# MAIN.net
KiCad netlist of a schematic drawn in Altium Designer
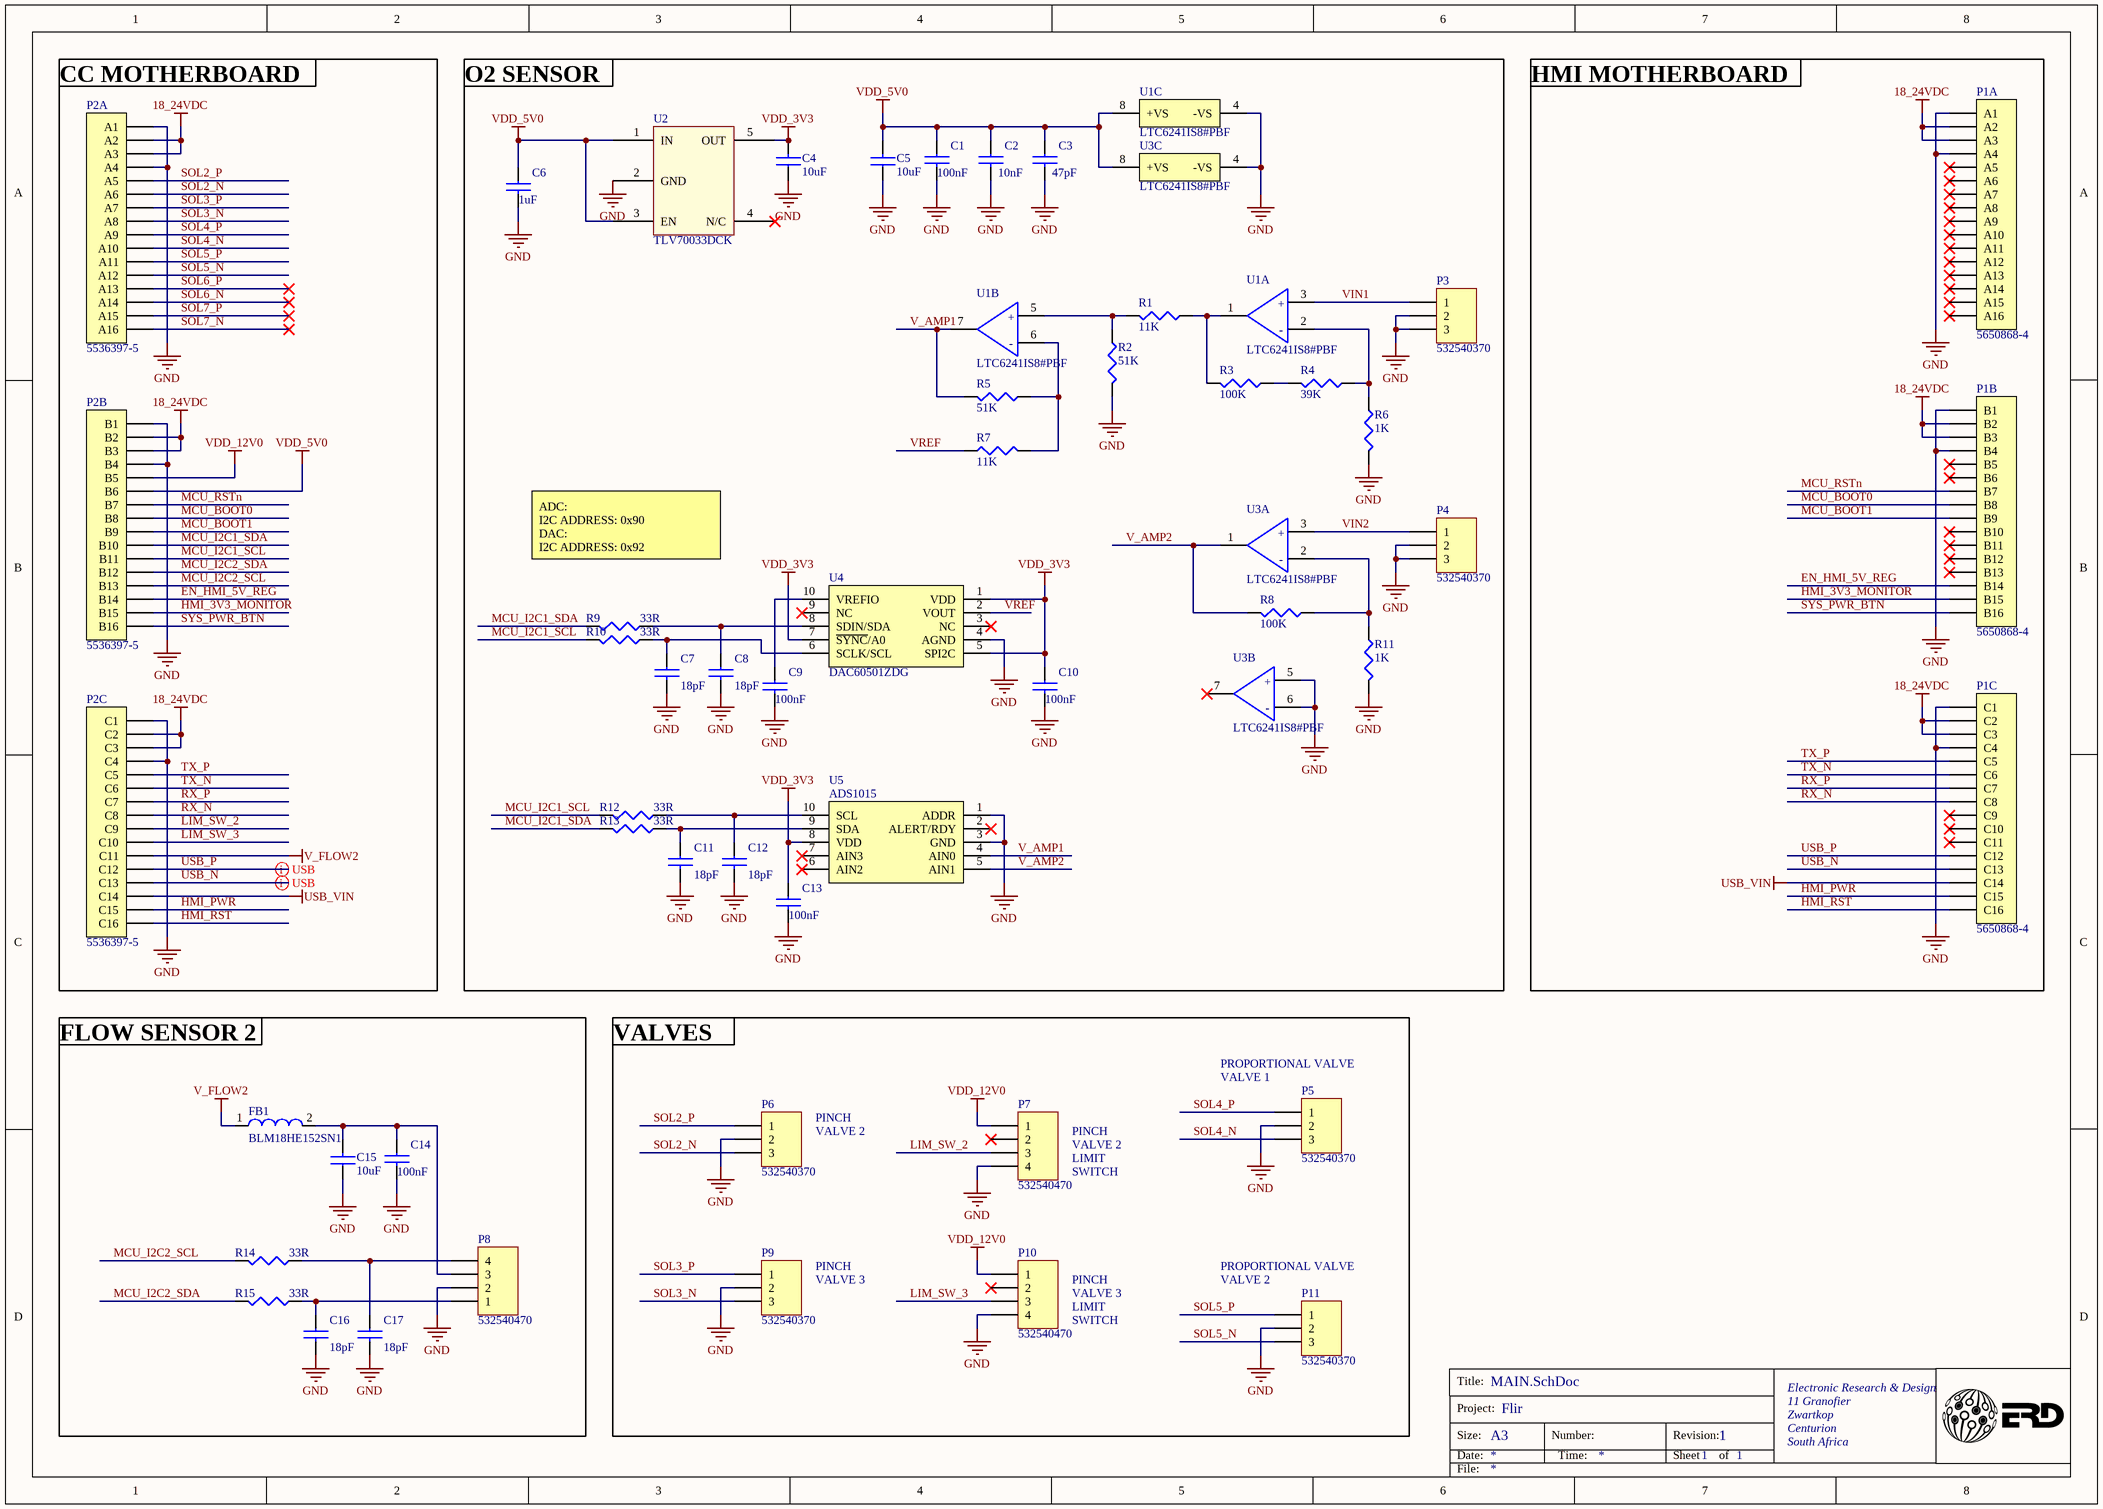
[diagram p0: MAIN.SchDoc]

(export (version "E")
  (design (tool "Eeschema 10.0.6"))
  (components
    (comp (ref "C1")
      (value "100nF")
      (footprint "CC0402")
      (description "CAP CER 0.1UF 50V 10% X7R 0402")
      (fields (field (name "MANUFACTURER") "Murata") (field (name "PART NUMBER") "GCM155R71H104KE02D"))
      (libsource (lib "ERD TiAm") (part "CAP CER 0.1UF 10V 10% X5R 0402"))
    )
    (comp (ref "C2")
      (value "10nF")
      (footprint "CC0402")
      (description "CAP CER 10NF 50V 10% X7R 0402")
      (fields (field (name "MANUFACTURER") "Murata") (field (name "PART NUMBER") "GRM155R71H103KA88J"))
      (libsource (lib "ERD TiAm") (part "CAP CER 0.1UF 10V 10% X5R 0402"))
    )
    (comp (ref "C3")
      (value "47pF")
      (footprint "CC0402")
      (description "CAP CER 47PF 50V 5% C0G/NP0 0402")
      (fields (field (name "MANUFACTURER") "Murata") (field (name "PART NUMBER") "GCM1555C1H470JA16D"))
      (libsource (lib "ERD TiAm") (part "CAP CER 0.1UF 10V 10% X5R 0402"))
    )
    (comp (ref "C4")
      (value "10uF")
      (footprint "CC0603")
      (description "CAP CER 10UF 25V 20% X5R 0603")
      (fields (field (name "MANUFACTURER") "Murata") (field (name "PARTNUMBER") "GRM188R61E106MA73D"))
      (libsource (lib "ERD TiAm") (part "CAP CER 0.1UF 10V 10% X5R 0402"))
    )
    (comp (ref "C5")
      (value "10uF")
      (footprint "CC0603")
      (description "CAP CER 10UF 25V 20% X5R 0603")
      (fields (field (name "MANUFACTURER") "Murata") (field (name "PARTNUMBER") "GRM188R61E106MA73D"))
      (libsource (lib "ERD TiAm") (part "CAP CER 0.1UF 10V 10% X5R 0402"))
    )
    (comp (ref "C6")
      (value "1uF")
      (footprint "CC0402")
      (description "CAP CER 1UF 10V 20% X5R 0402")
      (fields (field (name "MANUFACTURER") "Murata") (field (name "PART NUMBER") "GRM153R61A105ME95D"))
      (libsource (lib "ERD TiAm") (part "CAP CER 0.1UF 10V 10% X5R 0402"))
    )
    (comp (ref "C7")
      (value "18pF")
      (footprint "CC0402")
      (description "CAP CER 18pF 50V 5% C0G 0402")
      (fields (field (name "MANUFACTURER") "AVX") (field (name "PARTNUMBER") "GJM1555C1H180FB01D"))
      (libsource (lib "ERD TiAm") (part "CAP CER 2.2UF 6.3V 10% X5R 0402"))
    )
    (comp (ref "C8")
      (value "18pF")
      (footprint "CC0402")
      (description "CAP CER 18pF 50V 5% C0G 0402")
      (fields (field (name "MANUFACTURER") "AVX") (field (name "PARTNUMBER") "GJM1555C1H180FB01D"))
      (libsource (lib "ERD TiAm") (part "CAP CER 2.2UF 6.3V 10% X5R 0402"))
    )
    (comp (ref "C9")
      (value "100nF")
      (footprint "CC0402")
      (description "CAP CER 0.1UF 50V 10% X7R 0402")
      (fields (field (name "MANUFACTURER") "Murata") (field (name "PART NUMBER") "GCM155R71H104KE02D"))
      (libsource (lib "ERD TiAm") (part "CAP CER 0.1UF 10V 10% X5R 0402"))
    )
    (comp (ref "C10")
      (value "100nF")
      (footprint "CC0402")
      (description "CAP CER 0.1UF 50V 10% X7R 0402")
      (fields (field (name "MANUFACTURER") "Murata") (field (name "PART NUMBER") "GCM155R71H104KE02D"))
      (libsource (lib "ERD TiAm") (part "CAP CER 0.1UF 10V 10% X5R 0402"))
    )
    (comp (ref "C11")
      (value "18pF")
      (footprint "CC0402")
      (description "CAP CER 18pF 50V 5% C0G 0402")
      (fields (field (name "MANUFACTURER") "AVX") (field (name "PARTNUMBER") "GJM1555C1H180FB01D"))
      (libsource (lib "ERD TiAm") (part "CAP CER 2.2UF 6.3V 10% X5R 0402"))
    )
    (comp (ref "C12")
      (value "18pF")
      (footprint "CC0402")
      (description "CAP CER 18pF 50V 5% C0G 0402")
      (fields (field (name "MANUFACTURER") "AVX") (field (name "PARTNUMBER") "GJM1555C1H180FB01D"))
      (libsource (lib "ERD TiAm") (part "CAP CER 2.2UF 6.3V 10% X5R 0402"))
    )
    (comp (ref "C13")
      (value "100nF")
      (footprint "CC0402")
      (description "CAP CER 0.1UF 50V 10% X7R 0402")
      (fields (field (name "MANUFACTURER") "Murata") (field (name "PART NUMBER") "GCM155R71H104KE02D"))
      (libsource (lib "ERD TiAm") (part "CAP CER 0.1UF 10V 10% X5R 0402"))
    )
    (comp (ref "C14")
      (value "100nF")
      (footprint "CC0402")
      (description "CAP CER 0.1UF 50V 10% X7R 0402")
      (fields (field (name "MANUFACTURER") "Murata") (field (name "PART NUMBER") "GCM155R71H104KE02D"))
      (libsource (lib "ERD TiAm") (part "CAP CER 0.1UF 10V 10% X5R 0402"))
    )
    (comp (ref "C15")
      (value "10uF")
      (footprint "CC0603")
      (description "CAP CER 10UF 25V 20% X5R 0603")
      (fields (field (name "MANUFACTURER") "Murata") (field (name "PARTNUMBER") "GRM188R61E106MA73D"))
      (libsource (lib "ERD TiAm") (part "CAP CER 0.1UF 10V 10% X5R 0402"))
    )
    (comp (ref "C16")
      (value "18pF")
      (footprint "CC0402")
      (description "CAP CER 18pF 50V 5% C0G 0402")
      (fields (field (name "MANUFACTURER") "AVX") (field (name "PARTNUMBER") "GJM1555C1H180FB01D"))
      (libsource (lib "ERD TiAm") (part "CAP CER 2.2UF 6.3V 10% X5R 0402"))
    )
    (comp (ref "C17")
      (value "18pF")
      (footprint "CC0402")
      (description "CAP CER 18pF 50V 5% C0G 0402")
      (fields (field (name "MANUFACTURER") "AVX") (field (name "PARTNUMBER") "GJM1555C1H180FB01D"))
      (libsource (lib "ERD TiAm") (part "CAP CER 2.2UF 6.3V 10% X5R 0402"))
    )
    (comp (ref "FB1")
      (value "BLM18HE152SN1")
      (footprint "LC0603")
      (description "FERRITE, 500mA, 500mOHM, 0603")
      (libsource (lib "BEAGLEBONEBLACK_REV A5B") (part "FER_180_200_0"))
    )
    (comp (ref "P1")
      (value "5650868-4")
      (footprint "5650868-4_F_RA")
      (description "DIN-41612, R/2, 48-circuit, 3x16, 2.54mm pitch, RA, TH")
      (fields (field (name "MANUFACTURER") "TE Connectivity"))
      (libsource (lib "ERD TiAm") (part "DIN_41612_3x16"))
    )
    (comp (ref "P2")
      (value "5536397-5")
      (description "DIN-41612, C/2, 48-circuit, 3x16, 2.54mm pitch, TH")
      (fields (field (name "MANUFACTURER") "TE CONNECTIVITY"))
      (libsource (lib "DIN_designator") (part "DIN_41612_3x16"))
    )
    (comp (ref "P3")
      (value "532540370")
      (footprint "HDR1X3")
      (description "Header, RA, 3-circuit, 2mm pitch, TH")
      (fields (field (name "MANUFACTURER") "Molex"))
      (libsource (lib "Miscellaneous Connectors") (part "Header 3"))
    )
    (comp (ref "P4")
      (value "532540370")
      (footprint "HDR1X3")
      (description "Header, RA, 3-circuit, 2mm pitch, TH")
      (fields (field (name "MANUFACTURER") "Molex"))
      (libsource (lib "Miscellaneous Connectors") (part "Header 3"))
    )
    (comp (ref "P5")
      (value "532540370")
      (footprint "HDR1X3")
      (description "Header, RA, 3-circuit, 2mm pitch, TH")
      (fields (field (name "MANUFACTURER") "Molex"))
      (libsource (lib "Miscellaneous Connectors") (part "Header 3"))
    )
    (comp (ref "P6")
      (value "532540370")
      (footprint "HDR1X3")
      (description "Header, RA, 3-circuit, 2mm pitch, TH")
      (fields (field (name "MANUFACTURER") "Molex"))
      (libsource (lib "Miscellaneous Connectors") (part "Header 3"))
    )
    (comp (ref "P7")
      (value "532540470")
      (footprint "HDR1X4")
      (description "Header, RA, 4-circuit, 2mm pitch, TH")
      (fields (field (name "MANUFACTURER") "Molex"))
      (libsource (lib "Miscellaneous Connectors") (part "Header 4"))
    )
    (comp (ref "P8")
      (value "532540470")
      (footprint "HDR1X4")
      (description "Header, RA, 4-circuit, 2mm pitch, TH")
      (fields (field (name "MANUFACTURER") "Molex"))
      (libsource (lib "") (part "Header 4_1"))
    )
    (comp (ref "P9")
      (value "532540370")
      (footprint "HDR1X3")
      (description "Header, RA, 3-circuit, 2mm pitch, TH")
      (fields (field (name "MANUFACTURER") "Molex"))
      (libsource (lib "Miscellaneous Connectors") (part "Header 3"))
    )
    (comp (ref "P10")
      (value "532540470")
      (footprint "HDR1X4")
      (description "Header, RA, 4-circuit, 2mm pitch, TH")
      (fields (field (name "MANUFACTURER") "Molex"))
      (libsource (lib "Miscellaneous Connectors") (part "Header 4"))
    )
    (comp (ref "P11")
      (value "532540370")
      (footprint "HDR1X3")
      (description "Header, RA, 3-circuit, 2mm pitch, TH")
      (fields (field (name "MANUFACTURER") "Molex"))
      (libsource (lib "Miscellaneous Connectors") (part "Header 3"))
    )
    (comp (ref "R1")
      (value "11K")
      (footprint "RC0402")
      (description "RES, 11K OHM, 1/16W, 1%, 0402")
      (fields (field (name "MANUFACTURER") "Yageo") (field (name "PARTNUMBER") "RC0402FR-0711KL"))
      (libsource (lib "ERD TiAm") (part "RES_10K_1/16W_1%_0402"))
    )
    (comp (ref "R2")
      (value "51K")
      (footprint "RC0402")
      (description "RES, 51K OHM, 1/16W, 1%, 0402")
      (fields (field (name "MANUFACTURER") "Yageo") (field (name "PARTNUMBER") "RC0402FR-0751KL"))
      (libsource (lib "ERD TiAm") (part "RES_10K_1/16W_1%_0402"))
    )
    (comp (ref "R3")
      (value "100K")
      (footprint "RC0402")
      (description "RES, 100K OHM, 1/16W, 1%, 0402")
      (fields (field (name "MANUFACTURER") "Yageo") (field (name "PARTNUMBER") "RC0402FR-07100KL"))
      (libsource (lib "ERD TiAm") (part "RES_10K_1/16W_1%_0402"))
    )
    (comp (ref "R4")
      (value "39K")
      (footprint "RC0402")
      (description "RES, 39K OHM, 1/16W, 1%, 0402")
      (fields (field (name "MANUFACTURER") "Yageo") (field (name "PARTNUMBER") "RC0402FR-0739KL"))
      (libsource (lib "ERD TiAm") (part "RES_10K_1/16W_1%_0402"))
    )
    (comp (ref "R5")
      (value "51K")
      (footprint "RC0402")
      (description "RES, 51K OHM, 1/16W, 1%, 0402")
      (fields (field (name "MANUFACTURER") "Yageo") (field (name "PARTNUMBER") "RC0402FR-0751KL"))
      (libsource (lib "ERD TiAm") (part "RES_10K_1/16W_1%_0402"))
    )
    (comp (ref "R6")
      (value "1K")
      (footprint "RC0402")
      (description "RES, 1K OHM, 1/16W, 1%, 0402")
      (fields (field (name "MANUFACTURER") "Yageo") (field (name "PARTNUMBER") "RC0402FR-071KL"))
      (libsource (lib "ERD TiAm") (part "RES_10K_1/16W_1%_0402"))
    )
    (comp (ref "R7")
      (value "11K")
      (footprint "RC0402")
      (description "RES, 11K OHM, 1/16W, 1%, 0402")
      (fields (field (name "MANUFACTURER") "Yageo") (field (name "PARTNUMBER") "RC0402FR-0711KL"))
      (libsource (lib "ERD TiAm") (part "RES_10K_1/16W_1%_0402"))
    )
    (comp (ref "R8")
      (value "100K")
      (footprint "RC0402")
      (description "RES, 100K OHM, 1/16W, 1%, 0402")
      (fields (field (name "MANUFACTURER") "Yageo") (field (name "PARTNUMBER") "RC0402FR-07100KL"))
      (libsource (lib "ERD TiAm") (part "RES_10K_1/16W_1%_0402"))
    )
    (comp (ref "R9")
      (value "33R")
      (footprint "RC0402")
      (description "RES, 33 OHM, 1/16W, 1%, 0402")
      (fields (field (name "MANUFACTURER") "Yageo") (field (name "PARTNUMBER") "RC0402FR-0733RL"))
      (libsource (lib "ERD TiAm") (part "RES_10K_1/16W_1%_0402"))
    )
    (comp (ref "R10")
      (value "33R")
      (footprint "RC0402")
      (description "RES, 33 OHM, 1/16W, 1%, 0402")
      (fields (field (name "MANUFACTURER") "Yageo") (field (name "PARTNUMBER") "RC0402FR-0733RL"))
      (libsource (lib "ERD TiAm") (part "RES_10K_1/16W_1%_0402"))
    )
    (comp (ref "R11")
      (value "1K")
      (footprint "RC0402")
      (description "RES, 1K OHM, 1/16W, 1%, 0402")
      (fields (field (name "MANUFACTURER") "Yageo") (field (name "PARTNUMBER") "RC0402FR-071KL"))
      (libsource (lib "ERD TiAm") (part "RES_10K_1/16W_1%_0402"))
    )
    (comp (ref "R12")
      (value "33R")
      (footprint "RC0402")
      (description "RES, 33 OHM, 1/16W, 1%, 0402")
      (fields (field (name "MANUFACTURER") "Yageo") (field (name "PARTNUMBER") "RC0402FR-0733RL"))
      (libsource (lib "ERD TiAm") (part "RES_10K_1/16W_1%_0402"))
    )
    (comp (ref "R13")
      (value "33R")
      (footprint "RC0402")
      (description "RES, 33 OHM, 1/16W, 1%, 0402")
      (fields (field (name "MANUFACTURER") "Yageo") (field (name "PARTNUMBER") "RC0402FR-0733RL"))
      (libsource (lib "ERD TiAm") (part "RES_10K_1/16W_1%_0402"))
    )
    (comp (ref "R14")
      (value "33R")
      (footprint "RC0402")
      (description "RES, 33 OHM, 1/16W, 1%, 0402")
      (fields (field (name "MANUFACTURER") "Yageo") (field (name "PARTNUMBER") "RC0402FR-0733RL"))
      (libsource (lib "ERD TiAm") (part "RES_10K_1/16W_1%_0402"))
    )
    (comp (ref "R15")
      (value "33R")
      (footprint "RC0402")
      (description "RES, 33 OHM, 1/16W, 1%, 0402")
      (fields (field (name "MANUFACTURER") "Yageo") (field (name "PARTNUMBER") "RC0402FR-0733RL"))
      (libsource (lib "ERD TiAm") (part "RES_10K_1/16W_1%_0402"))
    )
    (comp (ref "U1")
      (value "LTC6241IS8#PBF")
      (footprint "SOIC-8")
      (description "Op-AMP, Dual, 18MHz, SOIC-8")
      (libsource (lib "") (part "AD823A_1"))
    )
    (comp (ref "U2")
      (value "TLV70033DCK")
      (footprint "SC-70-5")
      (description "LDO, 3.3V, 200mA, SC70-5")
      (libsource (lib "CameraModule") (part "TLV700"))
    )
    (comp (ref "U3")
      (value "LTC6241IS8#PBF")
      (footprint "SOIC-8")
      (description "Op-AMP, Dual, 18MHz, SOIC-8")
      (libsource (lib "") (part "AD823A_1"))
    )
    (comp (ref "U4")
      (value "DAC60501ZDG")
      (footprint "VSSOP-10")
      (description "DAC, 12-bit, I2C, VSSOP-10")
      (libsource (lib "ERD TiAm") (part "DAC60501"))
    )
    (comp (ref "U5")
      (value "ADS1015")
      (footprint "VSSOP-10")
      (description "ADC, 12-bit, I2C, 4-channel, VSSOP-10")
      (libsource (lib "ERD TiAm") (part "ADS1015"))
    )
  )
  (nets
    (net (code "1") (name "/EN_HMI_5V_REG") (class "Default")
      (node (ref "P1") (pin "30") (pinfunction "B14_30") (pintype "passive"))
      (node (ref "P2") (pin "30") (pinfunction "B14_30") (pintype "passive"))
    )
    (net (code "2") (name "/HMI_3V3_MONITOR") (class "Default")
      (node (ref "P1") (pin "31") (pinfunction "B15_31") (pintype "passive"))
      (node (ref "P2") (pin "31") (pinfunction "B15_31") (pintype "passive"))
    )
    (net (code "3") (name "/HMI_PWR") (class "Default")
      (node (ref "P1") (pin "47") (pinfunction "C15_47") (pintype "passive"))
      (node (ref "P2") (pin "47") (pinfunction "C15_47") (pintype "passive"))
    )
    (net (code "4") (name "/HMI_RST") (class "Default")
      (node (ref "P1") (pin "48") (pinfunction "C16_48") (pintype "passive"))
      (node (ref "P2") (pin "48") (pinfunction "C16_48") (pintype "passive"))
    )
    (net (code "5") (name "/LIM_SW_2") (class "Default")
      (node (ref "P2") (pin "41") (pinfunction "C9_41") (pintype "passive"))
      (node (ref "P7") (pin "3") (pinfunction "3_3") (pintype "passive"))
    )
    (net (code "6") (name "/LIM_SW_3") (class "Default")
      (node (ref "P10") (pin "3") (pinfunction "3_3") (pintype "passive"))
      (node (ref "P2") (pin "42") (pinfunction "C10_42") (pintype "passive"))
    )
    (net (code "7") (name "/MCU_BOOT0") (class "Default")
      (node (ref "P1") (pin "24") (pinfunction "B8_24") (pintype "passive"))
      (node (ref "P2") (pin "24") (pinfunction "B8_24") (pintype "passive"))
    )
    (net (code "8") (name "/MCU_BOOT1") (class "Default")
      (node (ref "P1") (pin "25") (pinfunction "B9_25") (pintype "passive"))
      (node (ref "P2") (pin "25") (pinfunction "B9_25") (pintype "passive"))
    )
    (net (code "9") (name "/MCU_I2C1_SCL") (class "Default")
      (node (ref "P2") (pin "27") (pinfunction "B11_27") (pintype "passive"))
      (node (ref "R10") (pin "2") (pinfunction "2_2") (pintype "passive"))
      (node (ref "R12") (pin "2") (pinfunction "2_2") (pintype "passive"))
    )
    (net (code "10") (name "/MCU_I2C1_SDA") (class "Default")
      (node (ref "P2") (pin "26") (pinfunction "B10_26") (pintype "passive"))
      (node (ref "R13") (pin "2") (pinfunction "2_2") (pintype "passive"))
      (node (ref "R9") (pin "2") (pinfunction "2_2") (pintype "passive"))
    )
    (net (code "11") (name "/MCU_I2C2_SCL") (class "Default")
      (node (ref "P2") (pin "29") (pinfunction "B13_29") (pintype "passive"))
      (node (ref "R14") (pin "2") (pinfunction "2_2") (pintype "passive"))
    )
    (net (code "12") (name "/MCU_I2C2_SDA") (class "Default")
      (node (ref "P2") (pin "28") (pinfunction "B12_28") (pintype "passive"))
      (node (ref "R15") (pin "2") (pinfunction "2_2") (pintype "passive"))
    )
    (net (code "13") (name "/MCU_RSTn") (class "Default")
      (node (ref "P1") (pin "23") (pinfunction "B7_23") (pintype "passive"))
      (node (ref "P2") (pin "23") (pinfunction "B7_23") (pintype "passive"))
    )
    (net (code "14") (name "/RX_N") (class "Default")
      (node (ref "P1") (pin "40") (pinfunction "C8_40") (pintype "passive"))
      (node (ref "P2") (pin "40") (pinfunction "C8_40") (pintype "passive"))
    )
    (net (code "15") (name "/RX_P") (class "Default")
      (node (ref "P1") (pin "39") (pinfunction "C7_39") (pintype "passive"))
      (node (ref "P2") (pin "39") (pinfunction "C7_39") (pintype "passive"))
    )
    (net (code "16") (name "/SOL2_N") (class "Default")
      (node (ref "P2") (pin "6") (pinfunction "A6_6") (pintype "passive"))
      (node (ref "P6") (pin "3") (pinfunction "3_3") (pintype "passive"))
    )
    (net (code "17") (name "/SOL2_P") (class "Default")
      (node (ref "P2") (pin "5") (pinfunction "A5_5") (pintype "passive"))
      (node (ref "P6") (pin "1") (pinfunction "1_1") (pintype "passive"))
    )
    (net (code "18") (name "/SOL3_N") (class "Default")
      (node (ref "P2") (pin "8") (pinfunction "A8_8") (pintype "passive"))
      (node (ref "P9") (pin "3") (pinfunction "3_3") (pintype "passive"))
    )
    (net (code "19") (name "/SOL3_P") (class "Default")
      (node (ref "P2") (pin "7") (pinfunction "A7_7") (pintype "passive"))
      (node (ref "P9") (pin "1") (pinfunction "1_1") (pintype "passive"))
    )
    (net (code "20") (name "/SOL4_N") (class "Default")
      (node (ref "P2") (pin "10") (pinfunction "A10_10") (pintype "passive"))
      (node (ref "P5") (pin "3") (pinfunction "3_3") (pintype "passive"))
    )
    (net (code "21") (name "/SOL4_P") (class "Default")
      (node (ref "P2") (pin "9") (pinfunction "A9_9") (pintype "passive"))
      (node (ref "P5") (pin "1") (pinfunction "1_1") (pintype "passive"))
    )
    (net (code "22") (name "/SOL5_N") (class "Default")
      (node (ref "P11") (pin "3") (pinfunction "3_3") (pintype "passive"))
      (node (ref "P2") (pin "12") (pinfunction "A12_12") (pintype "passive"))
    )
    (net (code "23") (name "/SOL5_P") (class "Default")
      (node (ref "P11") (pin "1") (pinfunction "1_1") (pintype "passive"))
      (node (ref "P2") (pin "11") (pinfunction "A11_11") (pintype "passive"))
    )
    (net (code "24") (name "/SOL6_N") (class "Default")
      (node (ref "P2") (pin "14") (pinfunction "A14_14") (pintype "passive+no_connect"))
    )
    (net (code "25") (name "/SOL6_P") (class "Default")
      (node (ref "P2") (pin "13") (pinfunction "A13_13") (pintype "passive+no_connect"))
    )
    (net (code "26") (name "/SOL7_N") (class "Default")
      (node (ref "P2") (pin "16") (pinfunction "A16_16") (pintype "passive+no_connect"))
    )
    (net (code "27") (name "/SOL7_P") (class "Default")
      (node (ref "P2") (pin "15") (pinfunction "A15_15") (pintype "passive+no_connect"))
    )
    (net (code "28") (name "/SYS_PWR_BTN") (class "Default")
      (node (ref "P1") (pin "32") (pinfunction "B16_32") (pintype "passive"))
      (node (ref "P2") (pin "32") (pinfunction "B16_32") (pintype "passive"))
    )
    (net (code "29") (name "/TX_N") (class "Default")
      (node (ref "P1") (pin "38") (pinfunction "C6_38") (pintype "passive"))
      (node (ref "P2") (pin "38") (pinfunction "C6_38") (pintype "passive"))
    )
    (net (code "30") (name "/TX_P") (class "Default")
      (node (ref "P1") (pin "37") (pinfunction "C5_37") (pintype "passive"))
      (node (ref "P2") (pin "37") (pinfunction "C5_37") (pintype "passive"))
    )
    (net (code "31") (name "/USB_N") (class "Default")
      (node (ref "P1") (pin "45") (pinfunction "C13_45") (pintype "passive"))
      (node (ref "P2") (pin "45") (pinfunction "C13_45") (pintype "passive"))
    )
    (net (code "32") (name "/USB_P") (class "Default")
      (node (ref "P1") (pin "44") (pinfunction "C12_44") (pintype "passive"))
      (node (ref "P2") (pin "44") (pinfunction "C12_44") (pintype "passive"))
    )
    (net (code "33") (name "/VIN1") (class "Default")
      (node (ref "P3") (pin "1") (pinfunction "1_1") (pintype "passive"))
      (node (ref "U1") (pin "3") (pinfunction "+IN1_3") (pintype "passive"))
    )
    (net (code "34") (name "/VIN2") (class "Default")
      (node (ref "P4") (pin "1") (pinfunction "1_1") (pintype "passive"))
      (node (ref "U3") (pin "3") (pinfunction "+IN1_3") (pintype "passive"))
    )
    (net (code "35") (name "/VREF") (class "Default")
      (node (ref "R7") (pin "1") (pinfunction "1_1") (pintype "passive"))
      (node (ref "U4") (pin "2") (pinfunction "VOUT_2") (pintype "passive"))
    )
    (net (code "36") (name "/V_AMP1") (class "Default")
      (node (ref "R5") (pin "2") (pinfunction "2_2") (pintype "passive"))
      (node (ref "U1") (pin "7") (pinfunction "OUT2_7") (pintype "passive"))
      (node (ref "U5") (pin "4") (pinfunction "AIN0_4") (pintype "passive"))
    )
    (net (code "37") (name "/V_AMP2") (class "Default")
      (node (ref "R8") (pin "2") (pinfunction "2_2") (pintype "passive"))
      (node (ref "U3") (pin "1") (pinfunction "OUT1_1") (pintype "passive"))
      (node (ref "U5") (pin "5") (pinfunction "AIN1_5") (pintype "passive"))
    )
    (net (code "38") (name "18_24VDC") (class "Default")
      (node (ref "P1") (pin "18") (pinfunction "B2_18") (pintype "passive"))
      (node (ref "P1") (pin "19") (pinfunction "B3_19") (pintype "passive"))
      (node (ref "P1") (pin "2") (pinfunction "A2_2") (pintype "passive"))
      (node (ref "P1") (pin "3") (pinfunction "A3_3") (pintype "passive"))
      (node (ref "P1") (pin "34") (pinfunction "C2_34") (pintype "passive"))
      (node (ref "P1") (pin "35") (pinfunction "C3_35") (pintype "passive"))
      (node (ref "P2") (pin "18") (pinfunction "B2_18") (pintype "passive"))
      (node (ref "P2") (pin "19") (pinfunction "B3_19") (pintype "passive"))
      (node (ref "P2") (pin "2") (pinfunction "A2_2") (pintype "passive"))
      (node (ref "P2") (pin "3") (pinfunction "A3_3") (pintype "passive"))
      (node (ref "P2") (pin "34") (pinfunction "C2_34") (pintype "passive"))
      (node (ref "P2") (pin "35") (pinfunction "C3_35") (pintype "passive"))
    )
    (net (code "39") (name "GND") (class "Default")
      (node (ref "C1") (pin "2") (pinfunction "2_2") (pintype "passive"))
      (node (ref "C10") (pin "2") (pinfunction "2_2") (pintype "passive"))
      (node (ref "C11") (pin "2") (pinfunction "2_2") (pintype "passive"))
      (node (ref "C12") (pin "2") (pinfunction "2_2") (pintype "passive"))
      (node (ref "C13") (pin "2") (pinfunction "2_2") (pintype "passive"))
      (node (ref "C14") (pin "2") (pinfunction "2_2") (pintype "passive"))
      (node (ref "C15") (pin "1") (pinfunction "1_1") (pintype "passive"))
      (node (ref "C16") (pin "2") (pinfunction "2_2") (pintype "passive"))
      (node (ref "C17") (pin "2") (pinfunction "2_2") (pintype "passive"))
      (node (ref "C2") (pin "2") (pinfunction "2_2") (pintype "passive"))
      (node (ref "C3") (pin "2") (pinfunction "2_2") (pintype "passive"))
      (node (ref "C4") (pin "1") (pinfunction "1_1") (pintype "passive"))
      (node (ref "C5") (pin "1") (pinfunction "1_1") (pintype "passive"))
      (node (ref "C6") (pin "2") (pinfunction "2_2") (pintype "passive"))
      (node (ref "C7") (pin "2") (pinfunction "2_2") (pintype "passive"))
      (node (ref "C8") (pin "2") (pinfunction "2_2") (pintype "passive"))
      (node (ref "C9") (pin "2") (pinfunction "2_2") (pintype "passive"))
      (node (ref "P1") (pin "1") (pinfunction "A1_1") (pintype "passive"))
      (node (ref "P1") (pin "17") (pinfunction "B1_17") (pintype "passive"))
      (node (ref "P1") (pin "20") (pinfunction "B4_20") (pintype "passive"))
      (node (ref "P1") (pin "33") (pinfunction "C1_33") (pintype "passive"))
      (node (ref "P1") (pin "36") (pinfunction "C4_36") (pintype "passive"))
      (node (ref "P1") (pin "4") (pinfunction "A4_4") (pintype "passive"))
      (node (ref "P10") (pin "4") (pinfunction "4_4") (pintype "passive"))
      (node (ref "P11") (pin "2") (pinfunction "2_2") (pintype "passive"))
      (node (ref "P2") (pin "1") (pinfunction "A1_1") (pintype "passive"))
      (node (ref "P2") (pin "17") (pinfunction "B1_17") (pintype "passive"))
      (node (ref "P2") (pin "20") (pinfunction "B4_20") (pintype "passive"))
      (node (ref "P2") (pin "33") (pinfunction "C1_33") (pintype "passive"))
      (node (ref "P2") (pin "36") (pinfunction "C4_36") (pintype "passive"))
      (node (ref "P2") (pin "4") (pinfunction "A4_4") (pintype "passive"))
      (node (ref "P3") (pin "2") (pinfunction "2_2") (pintype "passive"))
      (node (ref "P3") (pin "3") (pinfunction "3_3") (pintype "passive"))
      (node (ref "P4") (pin "2") (pinfunction "2_2") (pintype "passive"))
      (node (ref "P4") (pin "3") (pinfunction "3_3") (pintype "passive"))
      (node (ref "P5") (pin "2") (pinfunction "2_2") (pintype "passive"))
      (node (ref "P6") (pin "2") (pinfunction "2_2") (pintype "passive"))
      (node (ref "P7") (pin "4") (pinfunction "4_4") (pintype "passive"))
      (node (ref "P8") (pin "2") (pinfunction "2_2") (pintype "passive"))
      (node (ref "P9") (pin "2") (pinfunction "2_2") (pintype "passive"))
      (node (ref "R11") (pin "2") (pinfunction "2_2") (pintype "passive"))
      (node (ref "R2") (pin "2") (pinfunction "2_2") (pintype "passive"))
      (node (ref "R6") (pin "2") (pinfunction "2_2") (pintype "passive"))
      (node (ref "U1") (pin "4") (pinfunction "-VS_4") (pintype "passive"))
      (node (ref "U2") (pin "2") (pinfunction "GND_2") (pintype "passive"))
      (node (ref "U3") (pin "4") (pinfunction "-VS_4") (pintype "passive"))
      (node (ref "U3") (pin "5") (pinfunction "+IN2_5") (pintype "passive"))
      (node (ref "U3") (pin "6") (pinfunction "-IN2_6") (pintype "passive"))
      (node (ref "U4") (pin "4") (pinfunction "AGND_4") (pintype "passive"))
      (node (ref "U5") (pin "1") (pinfunction "ADDR_1") (pintype "passive"))
      (node (ref "U5") (pin "3") (pinfunction "GND_3") (pintype "passive"))
    )
    (net (code "40") (name "Net-(C14-Pad1)") (class "Default")
      (node (ref "C14") (pin "1") (pinfunction "1_1") (pintype "passive"))
      (node (ref "C15") (pin "2") (pinfunction "2_2") (pintype "passive"))
      (node (ref "FB1") (pin "2") (pinfunction "2_2") (pintype "passive"))
      (node (ref "P8") (pin "3") (pinfunction "3_3") (pintype "passive"))
    )
    (net (code "41") (name "Net-(C16-Pad1)") (class "Default")
      (node (ref "C16") (pin "1") (pinfunction "1_1") (pintype "passive"))
      (node (ref "P8") (pin "1") (pinfunction "1_1") (pintype "passive"))
      (node (ref "R15") (pin "1") (pinfunction "1_1") (pintype "passive"))
    )
    (net (code "42") (name "Net-(C17-Pad1)") (class "Default")
      (node (ref "C17") (pin "1") (pinfunction "1_1") (pintype "passive"))
      (node (ref "P8") (pin "4") (pinfunction "4_4") (pintype "passive"))
      (node (ref "R14") (pin "1") (pinfunction "1_1") (pintype "passive"))
    )
    (net (code "43") (name "Net-(R3-Pad1)") (class "Default")
      (node (ref "R3") (pin "1") (pinfunction "1_1") (pintype "passive"))
      (node (ref "R4") (pin "2") (pinfunction "2_2") (pintype "passive"))
    )
    (net (code "44") (name "Net-(U1A--IN1)") (class "Default")
      (node (ref "R4") (pin "1") (pinfunction "1_1") (pintype "passive"))
      (node (ref "R6") (pin "1") (pinfunction "1_1") (pintype "passive"))
      (node (ref "U1") (pin "2") (pinfunction "-IN1_2") (pintype "passive"))
    )
    (net (code "45") (name "Net-(U1A-OUT1)") (class "Default")
      (node (ref "R1") (pin "1") (pinfunction "1_1") (pintype "passive"))
      (node (ref "R3") (pin "2") (pinfunction "2_2") (pintype "passive"))
      (node (ref "U1") (pin "1") (pinfunction "OUT1_1") (pintype "passive"))
    )
    (net (code "46") (name "Net-(U1B-+IN2)") (class "Default")
      (node (ref "R1") (pin "2") (pinfunction "2_2") (pintype "passive"))
      (node (ref "R2") (pin "1") (pinfunction "1_1") (pintype "passive"))
      (node (ref "U1") (pin "5") (pinfunction "+IN2_5") (pintype "passive"))
    )
    (net (code "47") (name "Net-(U1B--IN2)") (class "Default")
      (node (ref "R5") (pin "1") (pinfunction "1_1") (pintype "passive"))
      (node (ref "R7") (pin "2") (pinfunction "2_2") (pintype "passive"))
      (node (ref "U1") (pin "6") (pinfunction "-IN2_6") (pintype "passive"))
    )
    (net (code "48") (name "Net-(U3A--IN1)") (class "Default")
      (node (ref "R11") (pin "1") (pinfunction "1_1") (pintype "passive"))
      (node (ref "R8") (pin "1") (pinfunction "1_1") (pintype "passive"))
      (node (ref "U3") (pin "2") (pinfunction "-IN1_2") (pintype "passive"))
    )
    (net (code "49") (name "Net-(U4-SCLK{slash}SCL)") (class "Default")
      (node (ref "C7") (pin "1") (pinfunction "1_1") (pintype "passive"))
      (node (ref "R10") (pin "1") (pinfunction "1_1") (pintype "passive"))
      (node (ref "U4") (pin "6") (pinfunction "SCLK/SCL_6") (pintype "passive"))
    )
    (net (code "50") (name "Net-(U4-SDIN{slash}SDA)") (class "Default")
      (node (ref "C8") (pin "1") (pinfunction "1_1") (pintype "passive"))
      (node (ref "R9") (pin "1") (pinfunction "1_1") (pintype "passive"))
      (node (ref "U4") (pin "8") (pinfunction "SDIN/SDA_8") (pintype "passive"))
    )
    (net (code "51") (name "Net-(U4-VREFIO)") (class "Default")
      (node (ref "C9") (pin "1") (pinfunction "1_1") (pintype "passive"))
      (node (ref "U4") (pin "10") (pinfunction "VREFIO_10") (pintype "passive"))
    )
    (net (code "52") (name "Net-(U5-SCL)") (class "Default")
      (node (ref "C12") (pin "1") (pinfunction "1_1") (pintype "passive"))
      (node (ref "R12") (pin "1") (pinfunction "1_1") (pintype "passive"))
      (node (ref "U5") (pin "10") (pinfunction "SCL_10") (pintype "passive"))
    )
    (net (code "53") (name "Net-(U5-SDA)") (class "Default")
      (node (ref "C11") (pin "1") (pinfunction "1_1") (pintype "passive"))
      (node (ref "R13") (pin "1") (pinfunction "1_1") (pintype "passive"))
      (node (ref "U5") (pin "9") (pinfunction "SDA_9") (pintype "passive"))
    )
    (net (code "54") (name "USB_VIN") (class "Default")
      (node (ref "P1") (pin "46") (pinfunction "C14_46") (pintype "passive"))
      (node (ref "P2") (pin "46") (pinfunction "C14_46") (pintype "passive"))
    )
    (net (code "55") (name "VDD_3V3") (class "Default")
      (node (ref "C10") (pin "1") (pinfunction "1_1") (pintype "passive"))
      (node (ref "C13") (pin "1") (pinfunction "1_1") (pintype "passive"))
      (node (ref "C4") (pin "2") (pinfunction "2_2") (pintype "passive"))
      (node (ref "U2") (pin "5") (pinfunction "OUT_5") (pintype "passive"))
      (node (ref "U4") (pin "1") (pinfunction "VDD_1") (pintype "passive"))
      (node (ref "U4") (pin "5") (pinfunction "SPI2C_5") (pintype "passive"))
      (node (ref "U4") (pin "7") (pinfunction "~{SYNC}/A0_7") (pintype "passive"))
      (node (ref "U5") (pin "8") (pinfunction "VDD_8") (pintype "passive"))
    )
    (net (code "56") (name "VDD_5V0") (class "Default")
      (node (ref "C1") (pin "1") (pinfunction "1_1") (pintype "passive"))
      (node (ref "C2") (pin "1") (pinfunction "1_1") (pintype "passive"))
      (node (ref "C3") (pin "1") (pinfunction "1_1") (pintype "passive"))
      (node (ref "C5") (pin "2") (pinfunction "2_2") (pintype "passive"))
      (node (ref "C6") (pin "1") (pinfunction "1_1") (pintype "passive"))
      (node (ref "P2") (pin "22") (pinfunction "B6_22") (pintype "passive"))
      (node (ref "U1") (pin "8") (pinfunction "+VS_8") (pintype "passive"))
      (node (ref "U2") (pin "1") (pinfunction "IN_1") (pintype "passive"))
      (node (ref "U2") (pin "3") (pinfunction "EN_3") (pintype "passive"))
      (node (ref "U3") (pin "8") (pinfunction "+VS_8") (pintype "passive"))
    )
    (net (code "57") (name "VDD_12V0") (class "Default")
      (node (ref "P10") (pin "1") (pinfunction "1_1") (pintype "passive"))
      (node (ref "P2") (pin "21") (pinfunction "B5_21") (pintype "passive"))
      (node (ref "P7") (pin "1") (pinfunction "1_1") (pintype "passive"))
    )
    (net (code "58") (name "V_FLOW2") (class "Default")
      (node (ref "FB1") (pin "1") (pinfunction "1_1") (pintype "passive"))
      (node (ref "P2") (pin "43") (pinfunction "C11_43") (pintype "passive"))
    )
    (net (code "59") (name "unconnected-(P1A-A5-Pad5)") (class "Default")
      (node (ref "P1") (pin "5") (pinfunction "A5_5") (pintype "passive+no_connect"))
    )
    (net (code "60") (name "unconnected-(P1A-A6-Pad6)") (class "Default")
      (node (ref "P1") (pin "6") (pinfunction "A6_6") (pintype "passive+no_connect"))
    )
    (net (code "61") (name "unconnected-(P1A-A7-Pad7)") (class "Default")
      (node (ref "P1") (pin "7") (pinfunction "A7_7") (pintype "passive+no_connect"))
    )
    (net (code "62") (name "unconnected-(P1A-A8-Pad8)") (class "Default")
      (node (ref "P1") (pin "8") (pinfunction "A8_8") (pintype "passive+no_connect"))
    )
    (net (code "63") (name "unconnected-(P1A-A9-Pad9)") (class "Default")
      (node (ref "P1") (pin "9") (pinfunction "A9_9") (pintype "passive+no_connect"))
    )
    (net (code "64") (name "unconnected-(P1A-A10-Pad10)") (class "Default")
      (node (ref "P1") (pin "10") (pinfunction "A10_10") (pintype "passive+no_connect"))
    )
    (net (code "65") (name "unconnected-(P1A-A11-Pad11)") (class "Default")
      (node (ref "P1") (pin "11") (pinfunction "A11_11") (pintype "passive+no_connect"))
    )
    (net (code "66") (name "unconnected-(P1A-A12-Pad12)") (class "Default")
      (node (ref "P1") (pin "12") (pinfunction "A12_12") (pintype "passive+no_connect"))
    )
    (net (code "67") (name "unconnected-(P1A-A13-Pad13)") (class "Default")
      (node (ref "P1") (pin "13") (pinfunction "A13_13") (pintype "passive+no_connect"))
    )
    (net (code "68") (name "unconnected-(P1A-A14-Pad14)") (class "Default")
      (node (ref "P1") (pin "14") (pinfunction "A14_14") (pintype "passive+no_connect"))
    )
    (net (code "69") (name "unconnected-(P1A-A15-Pad15)") (class "Default")
      (node (ref "P1") (pin "15") (pinfunction "A15_15") (pintype "passive+no_connect"))
    )
    (net (code "70") (name "unconnected-(P1A-A16-Pad16)") (class "Default")
      (node (ref "P1") (pin "16") (pinfunction "A16_16") (pintype "passive+no_connect"))
    )
    (net (code "71") (name "unconnected-(P1B-B5-Pad21)") (class "Default")
      (node (ref "P1") (pin "21") (pinfunction "B5_21") (pintype "passive+no_connect"))
    )
    (net (code "72") (name "unconnected-(P1B-B6-Pad22)") (class "Default")
      (node (ref "P1") (pin "22") (pinfunction "B6_22") (pintype "passive+no_connect"))
    )
    (net (code "73") (name "unconnected-(P1B-B10-Pad26)") (class "Default")
      (node (ref "P1") (pin "26") (pinfunction "B10_26") (pintype "passive+no_connect"))
    )
    (net (code "74") (name "unconnected-(P1B-B11-Pad27)") (class "Default")
      (node (ref "P1") (pin "27") (pinfunction "B11_27") (pintype "passive+no_connect"))
    )
    (net (code "75") (name "unconnected-(P1B-B12-Pad28)") (class "Default")
      (node (ref "P1") (pin "28") (pinfunction "B12_28") (pintype "passive+no_connect"))
    )
    (net (code "76") (name "unconnected-(P1B-B13-Pad29)") (class "Default")
      (node (ref "P1") (pin "29") (pinfunction "B13_29") (pintype "passive+no_connect"))
    )
    (net (code "77") (name "unconnected-(P1C-C9-Pad41)") (class "Default")
      (node (ref "P1") (pin "41") (pinfunction "C9_41") (pintype "passive+no_connect"))
    )
    (net (code "78") (name "unconnected-(P1C-C10-Pad42)") (class "Default")
      (node (ref "P1") (pin "42") (pinfunction "C10_42") (pintype "passive+no_connect"))
    )
    (net (code "79") (name "unconnected-(P1C-C11-Pad43)") (class "Default")
      (node (ref "P1") (pin "43") (pinfunction "C11_43") (pintype "passive+no_connect"))
    )
    (net (code "80") (name "unconnected-(P7-Pad2)") (class "Default")
      (node (ref "P7") (pin "2") (pinfunction "2_2") (pintype "passive+no_connect"))
    )
    (net (code "81") (name "unconnected-(P10-Pad2)") (class "Default")
      (node (ref "P10") (pin "2") (pinfunction "2_2") (pintype "passive+no_connect"))
    )
    (net (code "82") (name "unconnected-(U2-N{slash}C-Pad4)") (class "Default")
      (node (ref "U2") (pin "4") (pinfunction "N/C_4") (pintype "passive+no_connect"))
    )
    (net (code "83") (name "unconnected-(U3B-OUT2-Pad7)") (class "Default")
      (node (ref "U3") (pin "7") (pinfunction "OUT2_7") (pintype "passive+no_connect"))
    )
    (net (code "84") (name "unconnected-(U4-NC-Pad3)") (class "Default")
      (node (ref "U4") (pin "3") (pinfunction "NC_3") (pintype "passive+no_connect"))
    )
    (net (code "85") (name "unconnected-(U4-NC-Pad9)") (class "Default")
      (node (ref "U4") (pin "9") (pinfunction "NC_9") (pintype "passive+no_connect"))
    )
    (net (code "86") (name "unconnected-(U5-AIN2-Pad6)") (class "Default")
      (node (ref "U5") (pin "6") (pinfunction "AIN2_6") (pintype "passive+no_connect"))
    )
    (net (code "87") (name "unconnected-(U5-AIN3-Pad7)") (class "Default")
      (node (ref "U5") (pin "7") (pinfunction "AIN3_7") (pintype "passive+no_connect"))
    )
    (net (code "88") (name "unconnected-(U5-ALERT{slash}RDY-Pad2)") (class "Default")
      (node (ref "U5") (pin "2") (pinfunction "ALERT/RDY_2") (pintype "passive+no_connect"))
    )
  )
)
